# Adafruit_AW9523.net
KiCad netlist of a schematic drawn in EAGLE
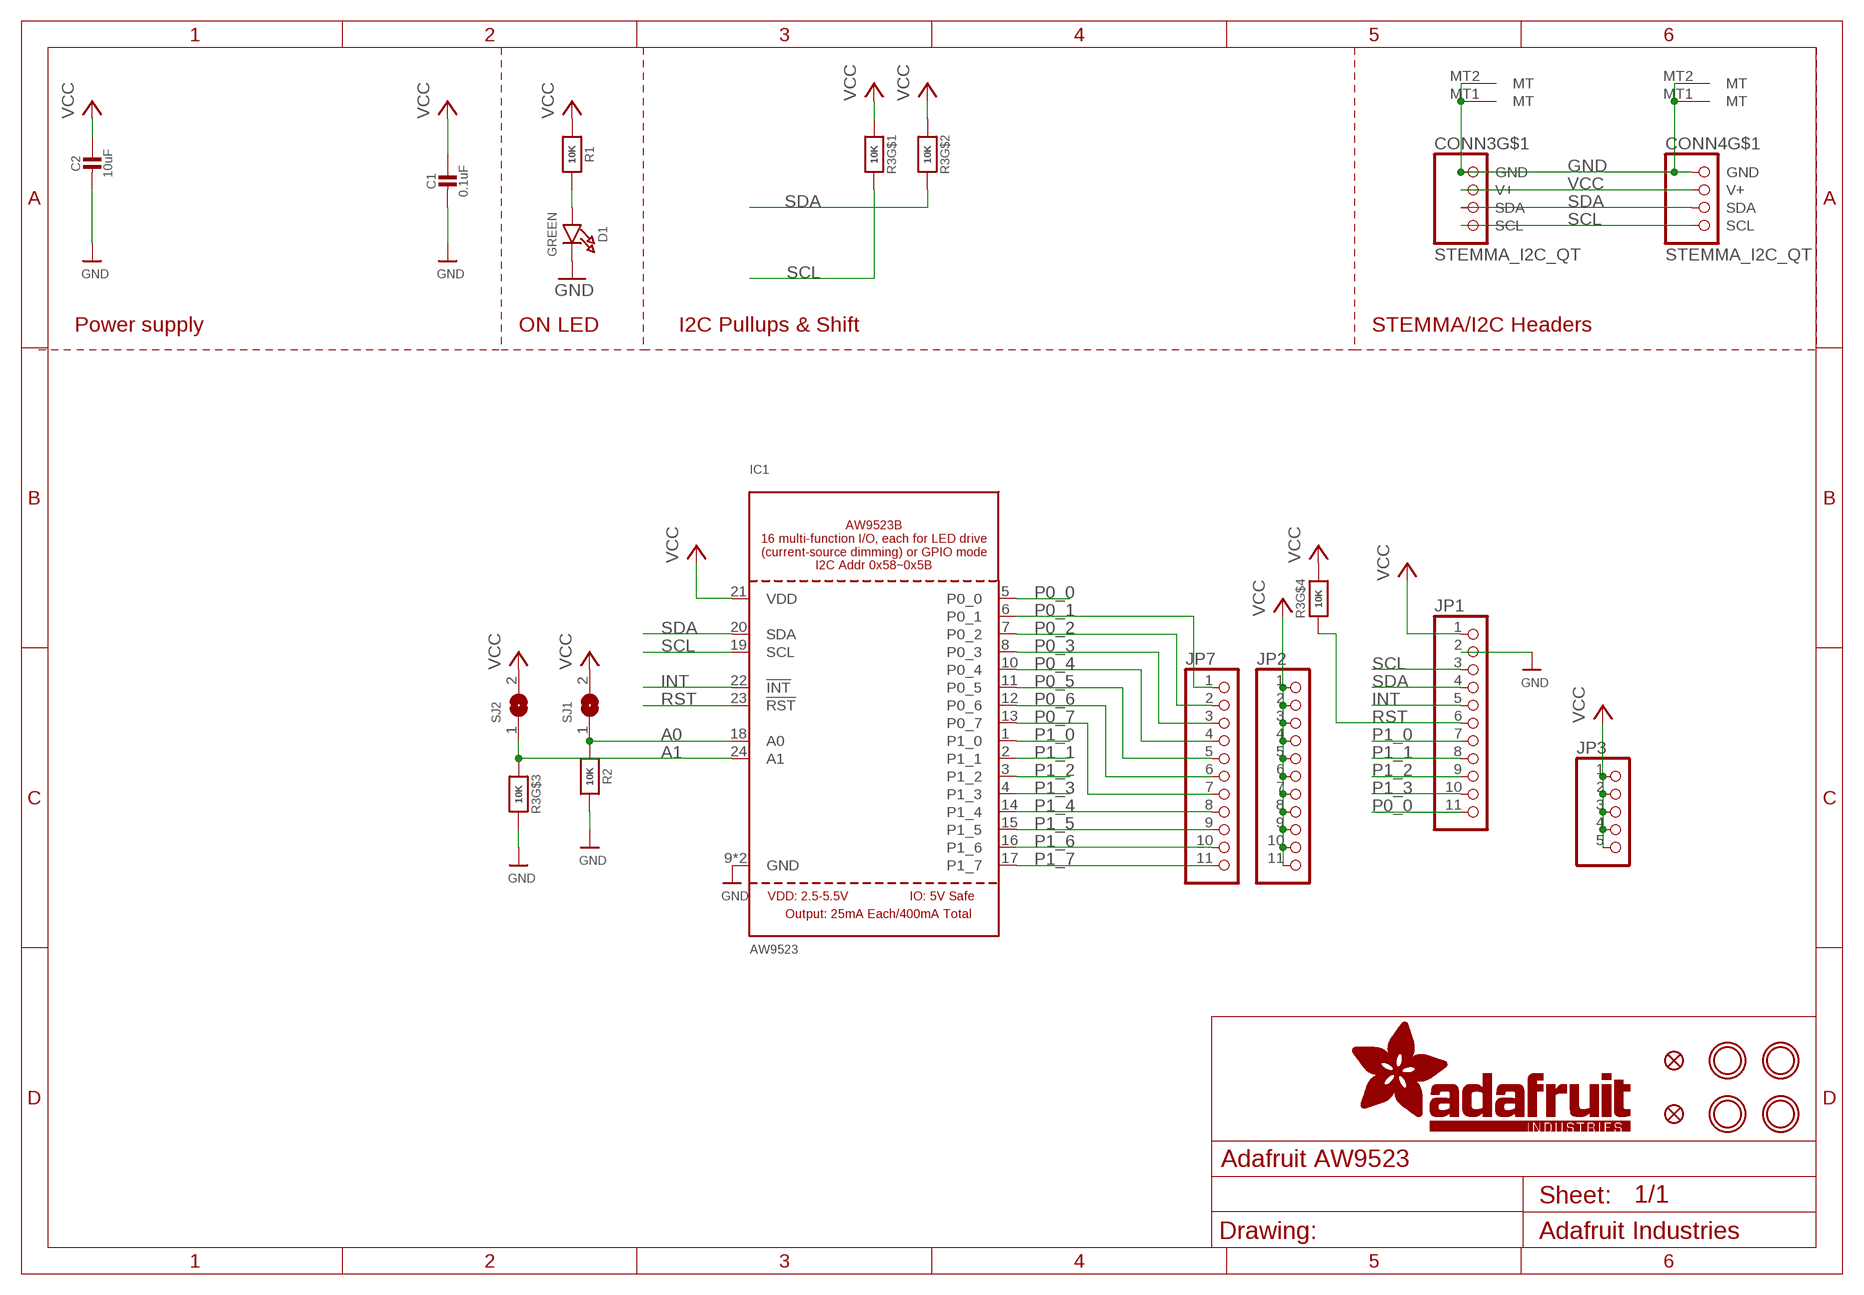
[diagram p0: schematic, sheet 1]

(export (version "E")
  (design (tool "Eeschema 10.0.6"))
  (components
    (comp (ref "C1")
      (value "0.1uF")
      (footprint "eagle-import:0603-NO")
      (libsource (lib "eagle-import") (part "CAP_CERAMIC0603_NO"))
    )
    (comp (ref "C2")
      (value "10uF")
      (footprint "eagle-import:0805-NO")
      (libsource (lib "eagle-import") (part "CAP_CERAMIC0805-NOOUTLINE"))
    )
    (comp (ref "CONN3")
      (value "STEMMA_I2C_QT")
      (footprint "eagle-import:JST_SH4")
      (libsource (lib "eagle-import") (part "STEMMA_I2C_QT"))
    )
    (comp (ref "CONN4")
      (value "STEMMA_I2C_QT")
      (footprint "eagle-import:JST_SH4")
      (libsource (lib "eagle-import") (part "STEMMA_I2C_QT"))
    )
    (comp (ref "D1")
      (value "GREEN")
      (footprint "eagle-import:CHIPLED_0603_NOOUTLINE")
      (libsource (lib "eagle-import") (part "LED0603_NOOUTLINE"))
    )
    (comp (ref "FID3")
      (value "FIDUCIAL_1MM")
      (footprint "eagle-import:FIDUCIAL_1MM")
      (libsource (lib "eagle-import") (part "FIDUCIAL_1MM"))
    )
    (comp (ref "FID4")
      (value "FIDUCIAL_1MM")
      (footprint "eagle-import:FIDUCIAL_1MM")
      (libsource (lib "eagle-import") (part "FIDUCIAL_1MM"))
    )
    (comp (ref "IC1")
      (value "AW9523")
      (footprint "eagle-import:QFN24_4MM_SMSC")
      (libsource (lib "eagle-import") (part "AW9523"))
    )
    (comp (ref "JP1")
      (value "HEADER-1X11")
      (footprint "eagle-import:1X11_ROUND")
      (libsource (lib "eagle-import") (part "HEADER-1X11"))
    )
    (comp (ref "JP2")
      (value "HEADER-1X11")
      (footprint "eagle-import:1X11_ROUND")
      (libsource (lib "eagle-import") (part "HEADER-1X11"))
    )
    (comp (ref "JP3")
      (value "HEADER-1X5ROUND")
      (footprint "eagle-import:1X05_ROUND")
      (libsource (lib "eagle-import") (part "HEADER-1X5ROUND"))
    )
    (comp (ref "JP7")
      (value "HEADER-1X11")
      (footprint "eagle-import:1X11_ROUND")
      (libsource (lib "eagle-import") (part "HEADER-1X11"))
    )
    (comp (ref "R1")
      (value "10K")
      (footprint "eagle-import:0603-NO")
      (libsource (lib "eagle-import") (part "RESISTOR_0603_NOOUT"))
    )
    (comp (ref "R2")
      (value "10K")
      (footprint "eagle-import:0603-NO")
      (libsource (lib "eagle-import") (part "RESISTOR_0603_NOOUT"))
    )
    (comp (ref "R3")
      (value "10K")
      (footprint "eagle-import:RESPACK_4X0603")
      (libsource (lib "eagle-import") (part "RESISTOR_4PACK"))
    )
    (comp (ref "SJ1")
      (value "SOLDERJUMPER")
      (footprint "eagle-import:SOLDERJUMPER_ARROW_NOPASTE")
      (libsource (lib "eagle-import") (part "SOLDERJUMPER"))
    )
    (comp (ref "SJ2")
      (value "SOLDERJUMPER")
      (footprint "eagle-import:SOLDERJUMPER_ARROW_NOPASTE")
      (libsource (lib "eagle-import") (part "SOLDERJUMPER"))
    )
    (comp (ref "U$1")
      (value "MOUNTINGHOLE2.5")
      (footprint "eagle-import:MOUNTINGHOLE_2.5_PLATED")
      (libsource (lib "eagle-import") (part "MOUNTINGHOLE2.5"))
    )
    (comp (ref "U$17")
      (value "MOUNTINGHOLE2.5")
      (footprint "eagle-import:MOUNTINGHOLE_2.5_PLATED")
      (libsource (lib "eagle-import") (part "MOUNTINGHOLE2.5"))
    )
    (comp (ref "U$19")
      (value "MOUNTINGHOLE2.5")
      (footprint "eagle-import:MOUNTINGHOLE_2.5_PLATED")
      (libsource (lib "eagle-import") (part "MOUNTINGHOLE2.5"))
    )
    (comp (ref "U$21")
      (value "MOUNTINGHOLE2.5")
      (footprint "eagle-import:MOUNTINGHOLE_2.5_PLATED")
      (libsource (lib "eagle-import") (part "MOUNTINGHOLE2.5"))
    )
  )
  (nets
    (net (code "1") (name "/A0") (class "Default")
      (node (ref "IC1") (pin "18") (pinfunction "A0_18") (pintype "input"))
      (node (ref "R2") (pin "1") (pinfunction "1_1") (pintype "passive"))
      (node (ref "SJ1") (pin "1") (pinfunction "1_1") (pintype "passive"))
    )
    (net (code "2") (name "/A1") (class "Default")
      (node (ref "IC1") (pin "24") (pinfunction "A1_24") (pintype "input"))
      (node (ref "R3") (pin "3") (pinfunction "1_3") (pintype "passive"))
      (node (ref "SJ2") (pin "1") (pinfunction "1_1") (pintype "passive"))
    )
    (net (code "3") (name "/INT") (class "Default")
      (node (ref "IC1") (pin "22") (pinfunction "~{INT}_22") (pintype "output"))
      (node (ref "JP1") (pin "5") (pinfunction "5_5") (pintype "passive"))
    )
    (net (code "4") (name "/P0_0") (class "Default")
      (node (ref "IC1") (pin "5") (pinfunction "P0_0_5") (pintype "bidirectional"))
      (node (ref "JP1") (pin "11") (pinfunction "11_11") (pintype "passive"))
    )
    (net (code "5") (name "/P0_1") (class "Default")
      (node (ref "IC1") (pin "6") (pinfunction "P0_1_6") (pintype "bidirectional"))
      (node (ref "JP7") (pin "1") (pinfunction "1_1") (pintype "passive"))
    )
    (net (code "6") (name "/P0_2") (class "Default")
      (node (ref "IC1") (pin "7") (pinfunction "P0_2_7") (pintype "bidirectional"))
      (node (ref "JP7") (pin "2") (pinfunction "2_2") (pintype "passive"))
    )
    (net (code "7") (name "/P0_3") (class "Default")
      (node (ref "IC1") (pin "8") (pinfunction "P0_3_8") (pintype "bidirectional"))
      (node (ref "JP7") (pin "3") (pinfunction "3_3") (pintype "passive"))
    )
    (net (code "8") (name "/P0_4") (class "Default")
      (node (ref "IC1") (pin "10") (pinfunction "P0_4_10") (pintype "bidirectional"))
      (node (ref "JP7") (pin "4") (pinfunction "4_4") (pintype "passive"))
    )
    (net (code "9") (name "/P0_5") (class "Default")
      (node (ref "IC1") (pin "11") (pinfunction "P0_5_11") (pintype "bidirectional"))
      (node (ref "JP7") (pin "5") (pinfunction "5_5") (pintype "passive"))
    )
    (net (code "10") (name "/P0_6") (class "Default")
      (node (ref "IC1") (pin "12") (pinfunction "P0_6_12") (pintype "bidirectional"))
      (node (ref "JP7") (pin "6") (pinfunction "6_6") (pintype "passive"))
    )
    (net (code "11") (name "/P0_7") (class "Default")
      (node (ref "IC1") (pin "13") (pinfunction "P0_7_13") (pintype "bidirectional"))
      (node (ref "JP7") (pin "7") (pinfunction "7_7") (pintype "passive"))
    )
    (net (code "12") (name "/P1_0") (class "Default")
      (node (ref "IC1") (pin "1") (pinfunction "P1_0_1") (pintype "bidirectional"))
      (node (ref "JP1") (pin "7") (pinfunction "7_7") (pintype "passive"))
    )
    (net (code "13") (name "/P1_1") (class "Default")
      (node (ref "IC1") (pin "2") (pinfunction "P1_1_2") (pintype "bidirectional"))
      (node (ref "JP1") (pin "8") (pinfunction "8_8") (pintype "passive"))
    )
    (net (code "14") (name "/P1_2") (class "Default")
      (node (ref "IC1") (pin "3") (pinfunction "P1_2_3") (pintype "bidirectional"))
      (node (ref "JP1") (pin "9") (pinfunction "9_9") (pintype "passive"))
    )
    (net (code "15") (name "/P1_3") (class "Default")
      (node (ref "IC1") (pin "4") (pinfunction "P1_3_4") (pintype "bidirectional"))
      (node (ref "JP1") (pin "10") (pinfunction "10_10") (pintype "passive"))
    )
    (net (code "16") (name "/P1_4") (class "Default")
      (node (ref "IC1") (pin "14") (pinfunction "P1_4_14") (pintype "bidirectional"))
      (node (ref "JP7") (pin "8") (pinfunction "8_8") (pintype "passive"))
    )
    (net (code "17") (name "/P1_5") (class "Default")
      (node (ref "IC1") (pin "15") (pinfunction "P1_5_15") (pintype "bidirectional"))
      (node (ref "JP7") (pin "9") (pinfunction "9_9") (pintype "passive"))
    )
    (net (code "18") (name "/P1_6") (class "Default")
      (node (ref "IC1") (pin "16") (pinfunction "P1_6_16") (pintype "bidirectional"))
      (node (ref "JP7") (pin "10") (pinfunction "10_10") (pintype "passive"))
    )
    (net (code "19") (name "/P1_7") (class "Default")
      (node (ref "IC1") (pin "17") (pinfunction "P1_7_17") (pintype "bidirectional"))
      (node (ref "JP7") (pin "11") (pinfunction "11_11") (pintype "passive"))
    )
    (net (code "20") (name "/RST") (class "Default")
      (node (ref "IC1") (pin "23") (pinfunction "~{RST}_23") (pintype "input"))
      (node (ref "JP1") (pin "6") (pinfunction "6_6") (pintype "passive"))
      (node (ref "R3") (pin "4") (pinfunction "1_4") (pintype "passive"))
    )
    (net (code "21") (name "/SCL") (class "Default")
      (node (ref "CONN3") (pin "4") (pinfunction "SCL_4") (pintype "passive"))
      (node (ref "CONN4") (pin "4") (pinfunction "SCL_4") (pintype "passive"))
      (node (ref "IC1") (pin "19") (pinfunction "SCL_19") (pintype "bidirectional"))
      (node (ref "JP1") (pin "3") (pinfunction "3_3") (pintype "passive"))
      (node (ref "R3") (pin "8") (pinfunction "2_8") (pintype "passive"))
    )
    (net (code "22") (name "/SDA") (class "Default")
      (node (ref "CONN3") (pin "3") (pinfunction "SDA_3") (pintype "passive"))
      (node (ref "CONN4") (pin "3") (pinfunction "SDA_3") (pintype "passive"))
      (node (ref "IC1") (pin "20") (pinfunction "SDA_20") (pintype "bidirectional"))
      (node (ref "JP1") (pin "4") (pinfunction "4_4") (pintype "passive"))
      (node (ref "R3") (pin "7") (pinfunction "2_7") (pintype "passive"))
    )
    (net (code "23") (name "GND") (class "Default")
      (node (ref "C1") (pin "2") (pinfunction "2_2") (pintype "passive"))
      (node (ref "C2") (pin "2") (pinfunction "2_2") (pintype "passive"))
      (node (ref "CONN3") (pin "1") (pinfunction "GND_1") (pintype "passive"))
      (node (ref "CONN3") (pin "MT1") (pinfunction "MT_MT1") (pintype "bidirectional"))
      (node (ref "CONN3") (pin "MT2") (pinfunction "MT_MT2") (pintype "bidirectional"))
      (node (ref "CONN4") (pin "1") (pinfunction "GND_1") (pintype "passive"))
      (node (ref "CONN4") (pin "MT1") (pinfunction "MT_MT1") (pintype "bidirectional"))
      (node (ref "CONN4") (pin "MT2") (pinfunction "MT_MT2") (pintype "bidirectional"))
      (node (ref "D1") (pin "C") (pinfunction "C_C") (pintype "passive"))
      (node (ref "IC1") (pin "9") (pinfunction "GND_9") (pintype "power_in"))
      (node (ref "IC1") (pin "THERM") (pinfunction "GND_THERM") (pintype "power_in"))
      (node (ref "JP1") (pin "2") (pinfunction "2_2") (pintype "passive"))
      (node (ref "R2") (pin "2") (pinfunction "2_2") (pintype "passive"))
      (node (ref "R3") (pin "6") (pinfunction "2_6") (pintype "passive"))
    )
    (net (code "24") (name "Net-(D1-PadA)") (class "Default")
      (node (ref "D1") (pin "A") (pinfunction "A_A") (pintype "passive"))
      (node (ref "R1") (pin "2") (pinfunction "2_2") (pintype "passive"))
    )
    (net (code "25") (name "VCC") (class "Default")
      (node (ref "C1") (pin "1") (pinfunction "1_1") (pintype "passive"))
      (node (ref "C2") (pin "1") (pinfunction "1_1") (pintype "passive"))
      (node (ref "CONN3") (pin "2") (pinfunction "V+_2") (pintype "passive"))
      (node (ref "CONN4") (pin "2") (pinfunction "V+_2") (pintype "passive"))
      (node (ref "IC1") (pin "21") (pinfunction "VDD_21") (pintype "power_in"))
      (node (ref "JP1") (pin "1") (pinfunction "1_1") (pintype "passive"))
      (node (ref "JP2") (pin "1") (pinfunction "1_1") (pintype "passive"))
      (node (ref "JP2") (pin "10") (pinfunction "10_10") (pintype "passive"))
      (node (ref "JP2") (pin "11") (pinfunction "11_11") (pintype "passive"))
      (node (ref "JP2") (pin "2") (pinfunction "2_2") (pintype "passive"))
      (node (ref "JP2") (pin "3") (pinfunction "3_3") (pintype "passive"))
      (node (ref "JP2") (pin "4") (pinfunction "4_4") (pintype "passive"))
      (node (ref "JP2") (pin "5") (pinfunction "5_5") (pintype "passive"))
      (node (ref "JP2") (pin "6") (pinfunction "6_6") (pintype "passive"))
      (node (ref "JP2") (pin "7") (pinfunction "7_7") (pintype "passive"))
      (node (ref "JP2") (pin "8") (pinfunction "8_8") (pintype "passive"))
      (node (ref "JP2") (pin "9") (pinfunction "9_9") (pintype "passive"))
      (node (ref "JP3") (pin "1") (pinfunction "1_1") (pintype "passive"))
      (node (ref "JP3") (pin "2") (pinfunction "2_2") (pintype "passive"))
      (node (ref "JP3") (pin "3") (pinfunction "3_3") (pintype "passive"))
      (node (ref "JP3") (pin "4") (pinfunction "4_4") (pintype "passive"))
      (node (ref "JP3") (pin "5") (pinfunction "5_5") (pintype "passive"))
      (node (ref "R1") (pin "1") (pinfunction "1_1") (pintype "passive"))
      (node (ref "R3") (pin "1") (pinfunction "1_1") (pintype "passive"))
      (node (ref "R3") (pin "2") (pinfunction "1_2") (pintype "passive"))
      (node (ref "R3") (pin "5") (pinfunction "2_5") (pintype "passive"))
      (node (ref "SJ1") (pin "2") (pinfunction "2_2") (pintype "passive"))
      (node (ref "SJ2") (pin "2") (pinfunction "2_2") (pintype "passive"))
    )
  )
)
